# ir.net
KiCad netlist of a schematic drawn in EAGLE
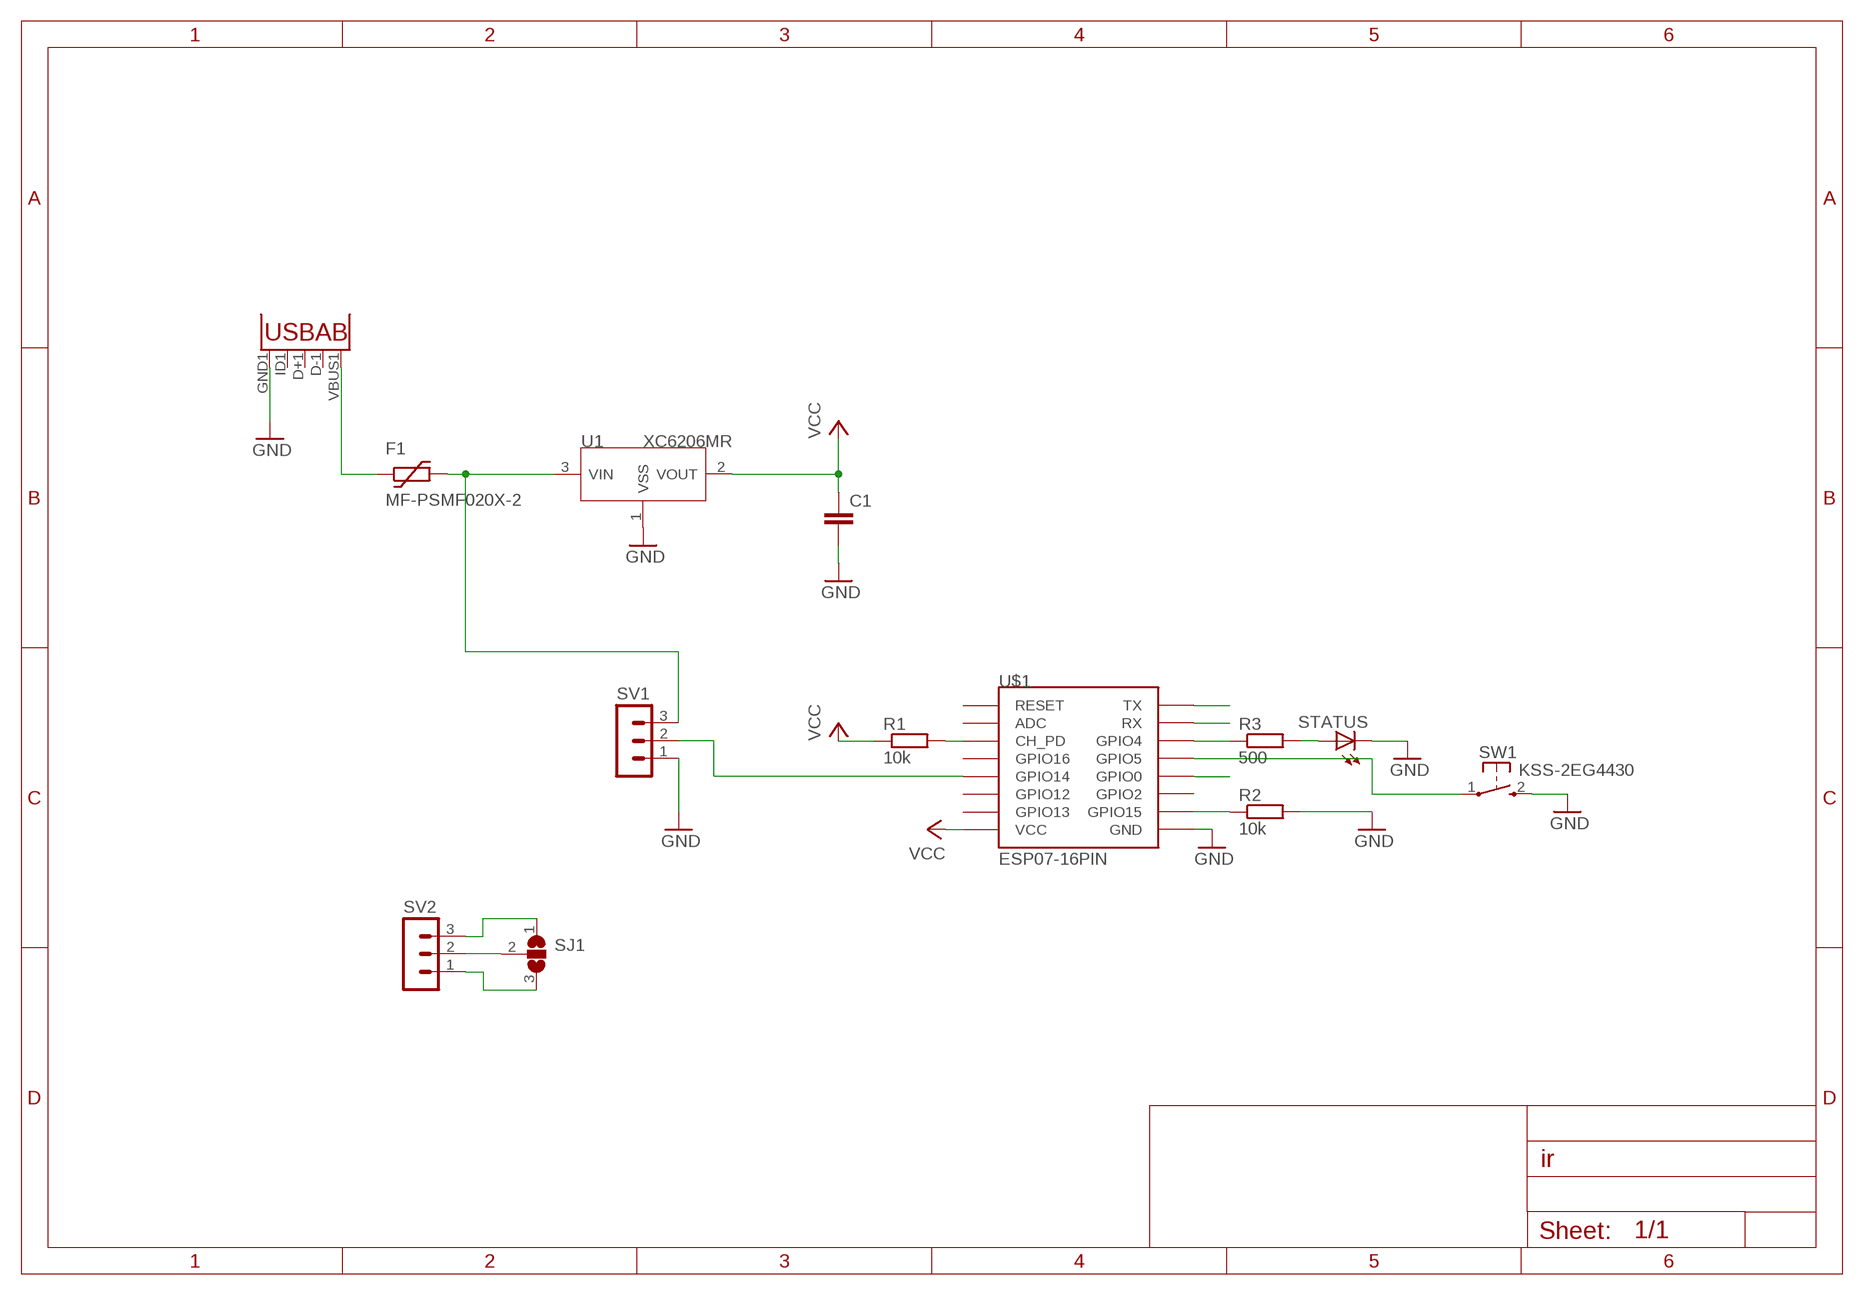
[diagram p0: schematic, sheet 1]

(export (version "E")
  (design (tool "Eeschema 10.0.6"))
  (components
    (comp (ref "C1")
      (value "C-EUC0805")
      (footprint "eagle-import:C0805")
      (libsource (lib "eagle-import") (part "C-EUC0805"))
    )
    (comp (ref "F1")
      (value "MF-PSMF020X-2")
      (footprint "eagle-import:0805L")
      (libsource (lib "eagle-import") (part "MF-PSMF020X-2"))
    )
    (comp (ref "R1")
      (value "10k")
      (footprint "eagle-import:R0805")
      (libsource (lib "eagle-import") (part "R-EU_R0805"))
    )
    (comp (ref "R2")
      (value "10k")
      (footprint "eagle-import:R0805")
      (libsource (lib "eagle-import") (part "R-EU_R0805"))
    )
    (comp (ref "R3")
      (value "500")
      (footprint "eagle-import:R0805")
      (libsource (lib "eagle-import") (part "R-EU_R0805"))
    )
    (comp (ref "SJ1")
      (value "SJ2W")
      (footprint "eagle-import:SJ_2")
      (libsource (lib "eagle-import") (part "SJ2W"))
    )
    (comp (ref "STATUS")
      (value "LEDCHIPLED_0805")
      (footprint "eagle-import:CHIPLED_0805")
      (libsource (lib "eagle-import") (part "LEDCHIPLED_0805"))
    )
    (comp (ref "SV1")
      (value "MA03-1")
      (footprint "eagle-import:MA03-1")
      (libsource (lib "eagle-import") (part "MA03-1"))
    )
    (comp (ref "SV2")
      (value "MA03-1")
      (footprint "eagle-import:MA03-1")
      (libsource (lib "eagle-import") (part "MA03-1"))
    )
    (comp (ref "SW1")
      (value "KSS-2EG4430")
      (footprint "eagle-import:KSS-2EG4430")
      (libsource (lib "eagle-import") (part "KSS-2EG4430"))
    )
    (comp (ref "U$1")
      (value "ESP07-16PIN")
      (footprint "eagle-import:ESP07-16PIN")
      (libsource (lib "eagle-import") (part "ESP07-16PIN"))
    )
    (comp (ref "U1")
      (value "XC6206MR")
      (footprint "eagle-import:SOT23")
      (libsource (lib "eagle-import") (part "XC6206MR"))
    )
    (comp (ref "U2")
      (value "USB\"\"")
      (footprint "eagle-import:USB-MICRO-SMD")
      (libsource (lib "eagle-import") (part "USB{dblquote}{dblquote}"))
    )
  )
  (nets
    (net (code "1") (name "GND") (class "Default")
      (node (ref "C1") (pin "2") (pinfunction "2_2") (pintype "passive"))
      (node (ref "R2") (pin "2") (pinfunction "2_2") (pintype "passive"))
      (node (ref "STATUS") (pin "C") (pinfunction "C_C") (pintype "passive"))
      (node (ref "SV1") (pin "1") (pinfunction "1_1") (pintype "passive"))
      (node (ref "SW1") (pin "2") (pinfunction "S_2") (pintype "passive"))
      (node (ref "U$1") (pin "GND") (pinfunction "GND_GND") (pintype "bidirectional"))
      (node (ref "U1") (pin "1") (pinfunction "VSS_1") (pintype "power_in"))
      (node (ref "U2") (pin "GND1") (pinfunction "GND_GND1") (pintype "bidirectional"))
    )
    (net (code "2") (name "Net-(R1-Pad2)") (class "Default")
      (node (ref "R1") (pin "2") (pinfunction "2_2") (pintype "passive"))
      (node (ref "U$1") (pin "CH_PD") (pinfunction "CH_PD_CH_PD") (pintype "bidirectional"))
    )
    (net (code "3") (name "Net-(R2-Pad1)") (class "Default")
      (node (ref "R2") (pin "1") (pinfunction "1_1") (pintype "passive"))
      (node (ref "U$1") (pin "GPIO15") (pinfunction "GPIO15_GPIO15") (pintype "bidirectional"))
    )
    (net (code "4") (name "Net-(R3-Pad1)") (class "Default")
      (node (ref "R3") (pin "1") (pinfunction "1_1") (pintype "passive"))
      (node (ref "U$1") (pin "GPIO4") (pinfunction "GPIO4_GPIO4") (pintype "bidirectional"))
    )
    (net (code "5") (name "Net-(R3-Pad2)") (class "Default")
      (node (ref "R3") (pin "2") (pinfunction "2_2") (pintype "passive"))
      (node (ref "STATUS") (pin "A") (pinfunction "A_A") (pintype "passive"))
    )
    (net (code "6") (name "Net-(SJ1-Pad1)") (class "Default")
      (node (ref "SJ1") (pin "1") (pinfunction "1_1") (pintype "passive"))
      (node (ref "SV2") (pin "3") (pinfunction "3_3") (pintype "passive"))
    )
    (net (code "7") (name "Net-(SJ1-Pad2)") (class "Default")
      (node (ref "SJ1") (pin "2") (pinfunction "2_2") (pintype "passive"))
      (node (ref "SV2") (pin "2") (pinfunction "2_2") (pintype "passive"))
    )
    (net (code "8") (name "Net-(SJ1-Pad3)") (class "Default")
      (node (ref "SJ1") (pin "3") (pinfunction "3_3") (pintype "passive"))
      (node (ref "SV2") (pin "1") (pinfunction "1_1") (pintype "passive"))
    )
    (net (code "9") (name "Net-(SV1-Pad2)") (class "Default")
      (node (ref "SV1") (pin "2") (pinfunction "2_2") (pintype "passive"))
      (node (ref "U$1") (pin "GPIO14") (pinfunction "GPIO14_GPIO14") (pintype "bidirectional"))
    )
    (net (code "10") (name "Net-(SW1-P)") (class "Default")
      (node (ref "SW1") (pin "1") (pinfunction "P_1") (pintype "passive"))
      (node (ref "U$1") (pin "GPIO5") (pinfunction "GPIO5_GPIO5") (pintype "bidirectional"))
    )
    (net (code "11") (name "Net-(U1-VIN)") (class "Default")
      (node (ref "F1") (pin "2") (pinfunction "2_2") (pintype "passive"))
      (node (ref "SV1") (pin "3") (pinfunction "3_3") (pintype "passive"))
      (node (ref "U1") (pin "3") (pinfunction "VIN_3") (pintype "input"))
    )
    (net (code "12") (name "Net-(U2-VBUS)") (class "Default")
      (node (ref "F1") (pin "1") (pinfunction "1_1") (pintype "passive"))
      (node (ref "U2") (pin "VBUS1") (pinfunction "VBUS_VBUS1") (pintype "bidirectional"))
    )
    (net (code "13") (name "VCC") (class "Default")
      (node (ref "C1") (pin "1") (pinfunction "1_1") (pintype "passive"))
      (node (ref "R1") (pin "1") (pinfunction "1_1") (pintype "passive"))
      (node (ref "U$1") (pin "VCC") (pinfunction "VCC_VCC") (pintype "bidirectional"))
      (node (ref "U1") (pin "2") (pinfunction "VOUT_2") (pintype "output"))
    )
    (net (code "14") (name "unconnected-(U$1-PadADC)") (class "Default")
      (node (ref "U$1") (pin "ADC") (pinfunction "ADC_ADC") (pintype "bidirectional"))
    )
    (net (code "15") (name "unconnected-(U$1-PadGPIO0)") (class "Default")
      (node (ref "U$1") (pin "GPIO0") (pinfunction "GPIO0_GPIO0") (pintype "bidirectional"))
    )
    (net (code "16") (name "unconnected-(U$1-PadGPIO2)") (class "Default")
      (node (ref "U$1") (pin "GPIO2") (pinfunction "GPIO2_GPIO2") (pintype "bidirectional"))
    )
    (net (code "17") (name "unconnected-(U$1-PadGPIO12)") (class "Default")
      (node (ref "U$1") (pin "GPIO12") (pinfunction "GPIO12_GPIO12") (pintype "bidirectional"))
    )
    (net (code "18") (name "unconnected-(U$1-PadGPIO13)") (class "Default")
      (node (ref "U$1") (pin "GPIO13") (pinfunction "GPIO13_GPIO13") (pintype "bidirectional"))
    )
    (net (code "19") (name "unconnected-(U$1-PadGPIO16)") (class "Default")
      (node (ref "U$1") (pin "GPIO16") (pinfunction "GPIO16_GPIO16") (pintype "bidirectional"))
    )
    (net (code "20") (name "unconnected-(U$1-PadRX)") (class "Default")
      (node (ref "U$1") (pin "RX") (pinfunction "RX_RX") (pintype "bidirectional"))
    )
    (net (code "21") (name "unconnected-(U$1-PadTX)") (class "Default")
      (node (ref "U$1") (pin "TX") (pinfunction "TX_TX") (pintype "bidirectional"))
    )
    (net (code "22") (name "unconnected-(U$1-RESET-PadREST)") (class "Default")
      (node (ref "U$1") (pin "REST") (pinfunction "RESET_REST") (pintype "bidirectional"))
    )
    (net (code "23") (name "unconnected-(U2-D+-PadD+1)") (class "Default")
      (node (ref "U2") (pin "D+1") (pinfunction "D+_D+1") (pintype "bidirectional"))
    )
    (net (code "24") (name "unconnected-(U2-D--PadD-1)") (class "Default")
      (node (ref "U2") (pin "D-1") (pinfunction "D-_D-1") (pintype "bidirectional"))
    )
    (net (code "25") (name "unconnected-(U2-USBID-PadID1)") (class "Default")
      (node (ref "U2") (pin "ID1") (pinfunction "USBID_ID1") (pintype "bidirectional"))
    )
  )
)
